# PCB_Timbangan.net
KiCad netlist of a schematic drawn in EasyEDA
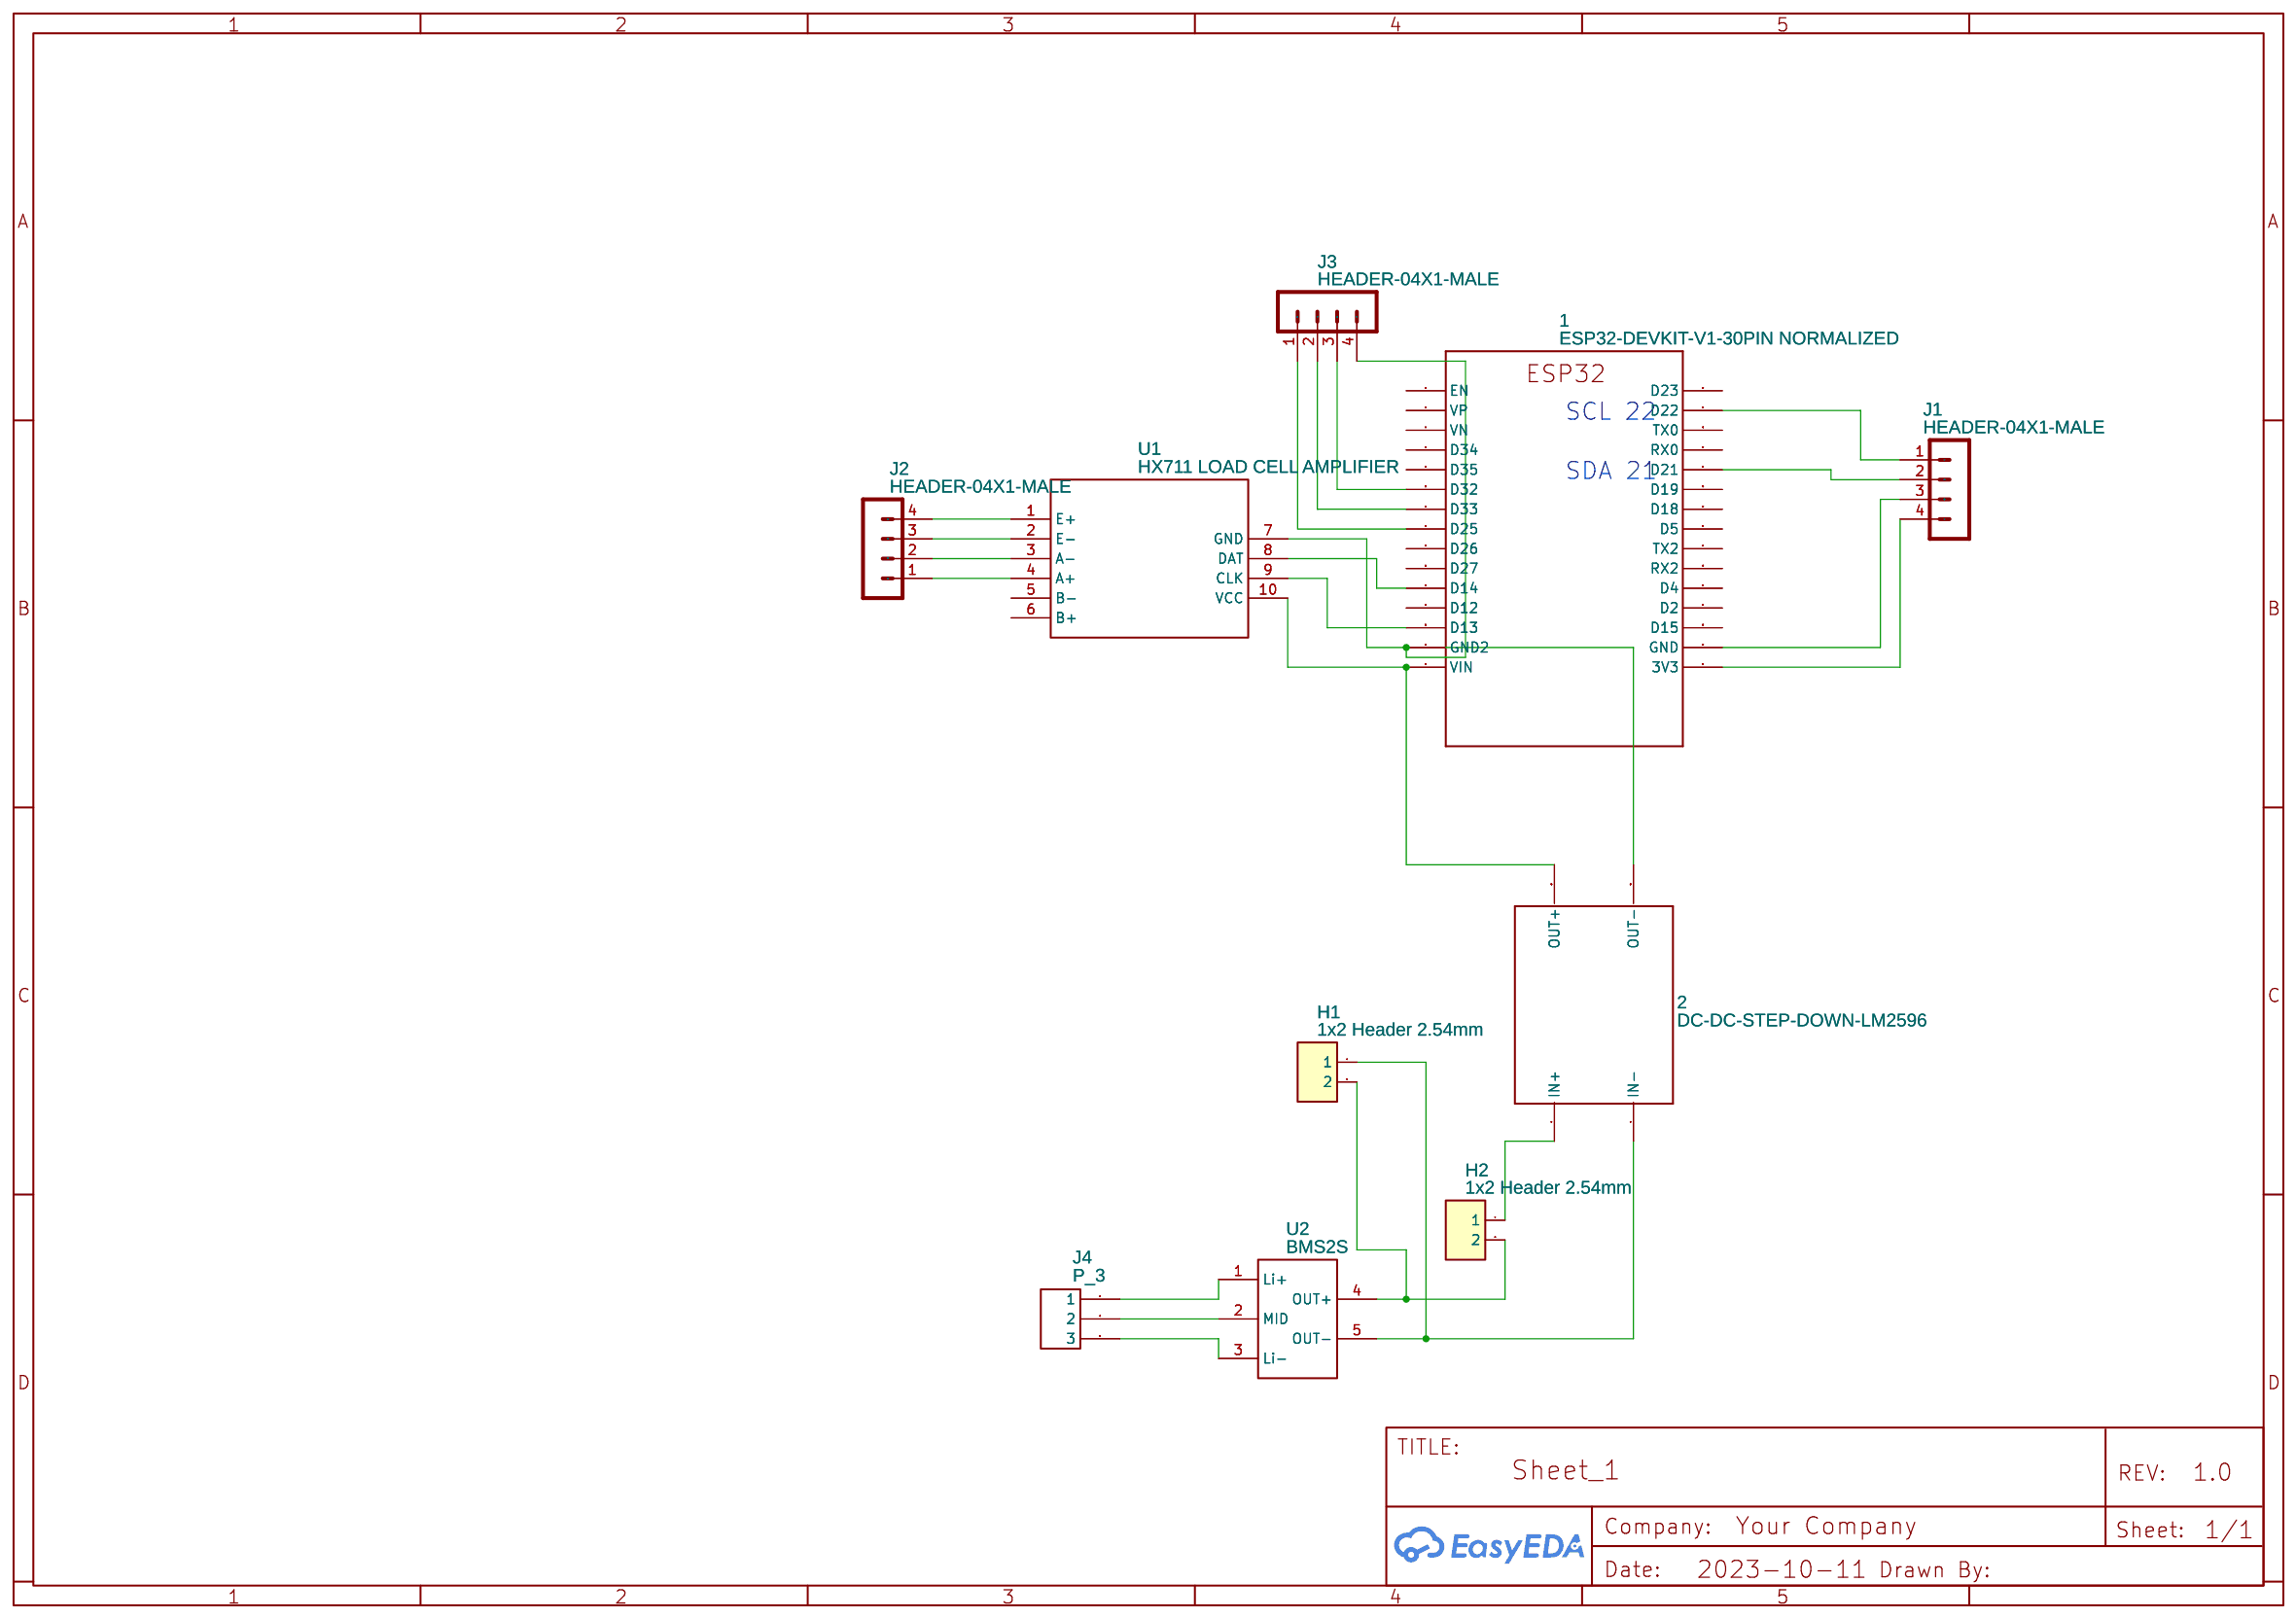
[diagram p0: schematic sheet]

(export (version "E")
  (design (tool "Eeschema 10.0.6"))
  (components
    (comp (ref "1")
      (value "ESP32-DEVKIT-V1-30PIN NORMALIZED")
      (libsource (lib "") (part "ESP32-DEVKIT-V1-30PIN"))
    )
    (comp (ref "2") (value "DC-DC-STEP-DOWN-LM2596") (libsource (lib "") (part "DC-DC-STEP-DOWN-LM2596")))
    (comp (ref "H1")
      (value "1x2 Header 2.54mm")
      (fields (field (name "Manufacturer Part") "New SchematicLib"))
      (libsource (lib "") (part "1x2 Header 2.54mm"))
    )
    (comp (ref "H2")
      (value "1x2 Header 2.54mm")
      (fields (field (name "Manufacturer Part") "New SchematicLib"))
      (libsource (lib "") (part "1x2 Header 2.54mm"))
    )
    (comp (ref "J1") (value "HEADER-04X1-MALE") (libsource (lib "") (part "HEADER-04X1-MALE_2")))
    (comp (ref "J2") (value "HEADER-04X1-MALE") (libsource (lib "") (part "HEADER-04X1-MALE")))
    (comp (ref "J3") (value "HEADER-04X1-MALE") (libsource (lib "") (part "HEADER-04X1-MALE_1")))
    (comp (ref "J4") (value "P_3") (libsource (lib "") (part "P_3")))
    (comp (ref "U1")
      (value "HX711 LOAD CELL AMPLIFIER")
      (libsource (lib "") (part "HX711 LOAD CELL AMPLIFIER"))
    )
    (comp (ref "U2") (value "BMS2S") (libsource (lib "") (part "BMS2S")))
  )
  (nets
    (net (code "1") (name "Net-(1-Pad3V3)") (class "Default")
      (node (ref "1") (pin "3V3") (pinfunction "3V3_3V3") (pintype "unspecified"))
      (node (ref "J1") (pin "4") (pinfunction "4_4") (pintype "unspecified"))
    )
    (net (code "2") (name "Net-(1-PadD21)") (class "Default")
      (node (ref "1") (pin "D21") (pinfunction "D21_D21") (pintype "unspecified"))
      (node (ref "J1") (pin "2") (pinfunction "2_2") (pintype "unspecified"))
    )
    (net (code "3") (name "Net-(1-PadD22)") (class "Default")
      (node (ref "1") (pin "D22") (pinfunction "D22_D22") (pintype "unspecified"))
      (node (ref "J1") (pin "1") (pinfunction "1_1") (pintype "unspecified"))
    )
    (net (code "4") (name "Net-(1-PadD25)") (class "Default")
      (node (ref "1") (pin "D25") (pinfunction "D25_D25") (pintype "unspecified"))
      (node (ref "J3") (pin "1") (pinfunction "1_1") (pintype "unspecified"))
    )
    (net (code "5") (name "Net-(1-PadD32)") (class "Default")
      (node (ref "1") (pin "D32") (pinfunction "D32_D32") (pintype "unspecified"))
      (node (ref "J3") (pin "3") (pinfunction "3_3") (pintype "unspecified"))
    )
    (net (code "6") (name "Net-(1-PadD33)") (class "Default")
      (node (ref "1") (pin "D33") (pinfunction "D33_D33") (pintype "unspecified"))
      (node (ref "J3") (pin "2") (pinfunction "2_2") (pintype "unspecified"))
    )
    (net (code "7") (name "Net-(1-PadGND)") (class "Default")
      (node (ref "1") (pin "GND") (pinfunction "GND_GND") (pintype "unspecified"))
      (node (ref "J1") (pin "3") (pinfunction "3_3") (pintype "unspecified"))
    )
    (net (code "8") (name "Net-(2-PadIN+)") (class "Default")
      (node (ref "2") (pin "IN+") (pinfunction "IN+_IN+") (pintype "bidirectional"))
      (node (ref "H2") (pin "1") (pinfunction "1_1") (pintype "unspecified"))
    )
    (net (code "9") (name "Net-(U1-A+)") (class "Default")
      (node (ref "J2") (pin "1") (pinfunction "1_1") (pintype "unspecified"))
      (node (ref "U1") (pin "4") (pinfunction "A+_4") (pintype "unspecified"))
    )
    (net (code "10") (name "Net-(U1-A-)") (class "Default")
      (node (ref "J2") (pin "2") (pinfunction "2_2") (pintype "unspecified"))
      (node (ref "U1") (pin "3") (pinfunction "A-_3") (pintype "unspecified"))
    )
    (net (code "11") (name "Net-(U1-CLK)") (class "Default")
      (node (ref "1") (pin "D13") (pinfunction "D13_D13") (pintype "unspecified"))
      (node (ref "U1") (pin "9") (pinfunction "CLK_9") (pintype "unspecified"))
    )
    (net (code "12") (name "Net-(U1-DAT)") (class "Default")
      (node (ref "1") (pin "D14") (pinfunction "D14_D14") (pintype "unspecified"))
      (node (ref "U1") (pin "8") (pinfunction "DAT_8") (pintype "unspecified"))
    )
    (net (code "13") (name "Net-(U1-E+)") (class "Default")
      (node (ref "J2") (pin "4") (pinfunction "4_4") (pintype "unspecified"))
      (node (ref "U1") (pin "1") (pinfunction "E+_1") (pintype "unspecified"))
    )
    (net (code "14") (name "Net-(U1-E-)") (class "Default")
      (node (ref "J2") (pin "3") (pinfunction "3_3") (pintype "unspecified"))
      (node (ref "U1") (pin "2") (pinfunction "E-_2") (pintype "unspecified"))
    )
    (net (code "15") (name "Net-(U1-GND)") (class "Default")
      (node (ref "1") (pin "GND2") (pinfunction "GND2_GND2") (pintype "unspecified"))
      (node (ref "2") (pin "OUT-") (pinfunction "OUT-_OUT-") (pintype "bidirectional"))
      (node (ref "J3") (pin "4") (pinfunction "4_4") (pintype "unspecified"))
      (node (ref "U1") (pin "7") (pinfunction "GND_7") (pintype "unspecified"))
    )
    (net (code "16") (name "Net-(U1-VCC)") (class "Default")
      (node (ref "1") (pin "VIN") (pinfunction "VIN_VIN") (pintype "unspecified"))
      (node (ref "2") (pin "OUT+") (pinfunction "OUT+_OUT+") (pintype "bidirectional"))
      (node (ref "U1") (pin "10") (pinfunction "VCC_10") (pintype "unspecified"))
    )
    (net (code "17") (name "Net-(U2-Li+)") (class "Default")
      (node (ref "J4") (pin "1") (pinfunction "1_1") (pintype "unspecified"))
      (node (ref "U2") (pin "1") (pinfunction "Li+_1") (pintype "unspecified"))
    )
    (net (code "18") (name "Net-(U2-Li-)") (class "Default")
      (node (ref "J4") (pin "3") (pinfunction "3_3") (pintype "unspecified"))
      (node (ref "U2") (pin "3") (pinfunction "Li-_3") (pintype "unspecified"))
    )
    (net (code "19") (name "Net-(U2-MID)") (class "Default")
      (node (ref "J4") (pin "2") (pinfunction "2_2") (pintype "unspecified"))
      (node (ref "U2") (pin "2") (pinfunction "MID_2") (pintype "unspecified"))
    )
    (net (code "20") (name "Net-(U2-OUT+)") (class "Default")
      (node (ref "H1") (pin "2") (pinfunction "2_2") (pintype "unspecified"))
      (node (ref "H2") (pin "2") (pinfunction "2_2") (pintype "unspecified"))
      (node (ref "U2") (pin "4") (pinfunction "OUT+_4") (pintype "unspecified"))
    )
    (net (code "21") (name "Net-(U2-OUT-)") (class "Default")
      (node (ref "2") (pin "IN-") (pinfunction "IN-_IN-") (pintype "bidirectional"))
      (node (ref "H1") (pin "1") (pinfunction "1_1") (pintype "unspecified"))
      (node (ref "U2") (pin "5") (pinfunction "OUT-_5") (pintype "unspecified"))
    )
    (net (code "22") (name "unconnected-(1-PadD2)") (class "Default")
      (node (ref "1") (pin "D2") (pinfunction "D2_D2") (pintype "unspecified"))
    )
    (net (code "23") (name "unconnected-(1-PadD4)") (class "Default")
      (node (ref "1") (pin "D4") (pinfunction "D4_D4") (pintype "unspecified"))
    )
    (net (code "24") (name "unconnected-(1-PadD5)") (class "Default")
      (node (ref "1") (pin "D5") (pinfunction "D5_D5") (pintype "unspecified"))
    )
    (net (code "25") (name "unconnected-(1-PadD12)") (class "Default")
      (node (ref "1") (pin "D12") (pinfunction "D12_D12") (pintype "unspecified"))
    )
    (net (code "26") (name "unconnected-(1-PadD15)") (class "Default")
      (node (ref "1") (pin "D15") (pinfunction "D15_D15") (pintype "unspecified"))
    )
    (net (code "27") (name "unconnected-(1-PadD18)") (class "Default")
      (node (ref "1") (pin "D18") (pinfunction "D18_D18") (pintype "unspecified"))
    )
    (net (code "28") (name "unconnected-(1-PadD19)") (class "Default")
      (node (ref "1") (pin "D19") (pinfunction "D19_D19") (pintype "unspecified"))
    )
    (net (code "29") (name "unconnected-(1-PadD23)") (class "Default")
      (node (ref "1") (pin "D23") (pinfunction "D23_D23") (pintype "unspecified"))
    )
    (net (code "30") (name "unconnected-(1-PadD26)") (class "Default")
      (node (ref "1") (pin "D26") (pinfunction "D26_D26") (pintype "unspecified"))
    )
    (net (code "31") (name "unconnected-(1-PadD27)") (class "Default")
      (node (ref "1") (pin "D27") (pinfunction "D27_D27") (pintype "unspecified"))
    )
    (net (code "32") (name "unconnected-(1-PadD34)") (class "Default")
      (node (ref "1") (pin "D34") (pinfunction "D34_D34") (pintype "unspecified"))
    )
    (net (code "33") (name "unconnected-(1-PadD35)") (class "Default")
      (node (ref "1") (pin "D35") (pinfunction "D35_D35") (pintype "unspecified"))
    )
    (net (code "34") (name "unconnected-(1-PadEN)") (class "Default")
      (node (ref "1") (pin "EN") (pinfunction "EN_EN") (pintype "unspecified"))
    )
    (net (code "35") (name "unconnected-(1-PadRX0)") (class "Default")
      (node (ref "1") (pin "RX0") (pinfunction "RX0_RX0") (pintype "unspecified"))
    )
    (net (code "36") (name "unconnected-(1-PadRX2)") (class "Default")
      (node (ref "1") (pin "RX2") (pinfunction "RX2_RX2") (pintype "unspecified"))
    )
    (net (code "37") (name "unconnected-(1-PadTX0)") (class "Default")
      (node (ref "1") (pin "TX0") (pinfunction "TX0_TX0") (pintype "unspecified"))
    )
    (net (code "38") (name "unconnected-(1-PadTX2)") (class "Default")
      (node (ref "1") (pin "TX2") (pinfunction "TX2_TX2") (pintype "unspecified"))
    )
    (net (code "39") (name "unconnected-(1-PadVN)") (class "Default")
      (node (ref "1") (pin "VN") (pinfunction "VN_VN") (pintype "unspecified"))
    )
    (net (code "40") (name "unconnected-(1-PadVP)") (class "Default")
      (node (ref "1") (pin "VP") (pinfunction "VP_VP") (pintype "unspecified"))
    )
    (net (code "41") (name "unconnected-(U1-B+-Pad6)") (class "Default")
      (node (ref "U1") (pin "6") (pinfunction "B+_6") (pintype "unspecified"))
    )
    (net (code "42") (name "unconnected-(U1-B--Pad5)") (class "Default")
      (node (ref "U1") (pin "5") (pinfunction "B-_5") (pintype "unspecified"))
    )
  )
)
